# Buck.net
KiCad netlist of a schematic drawn in Altium Designer
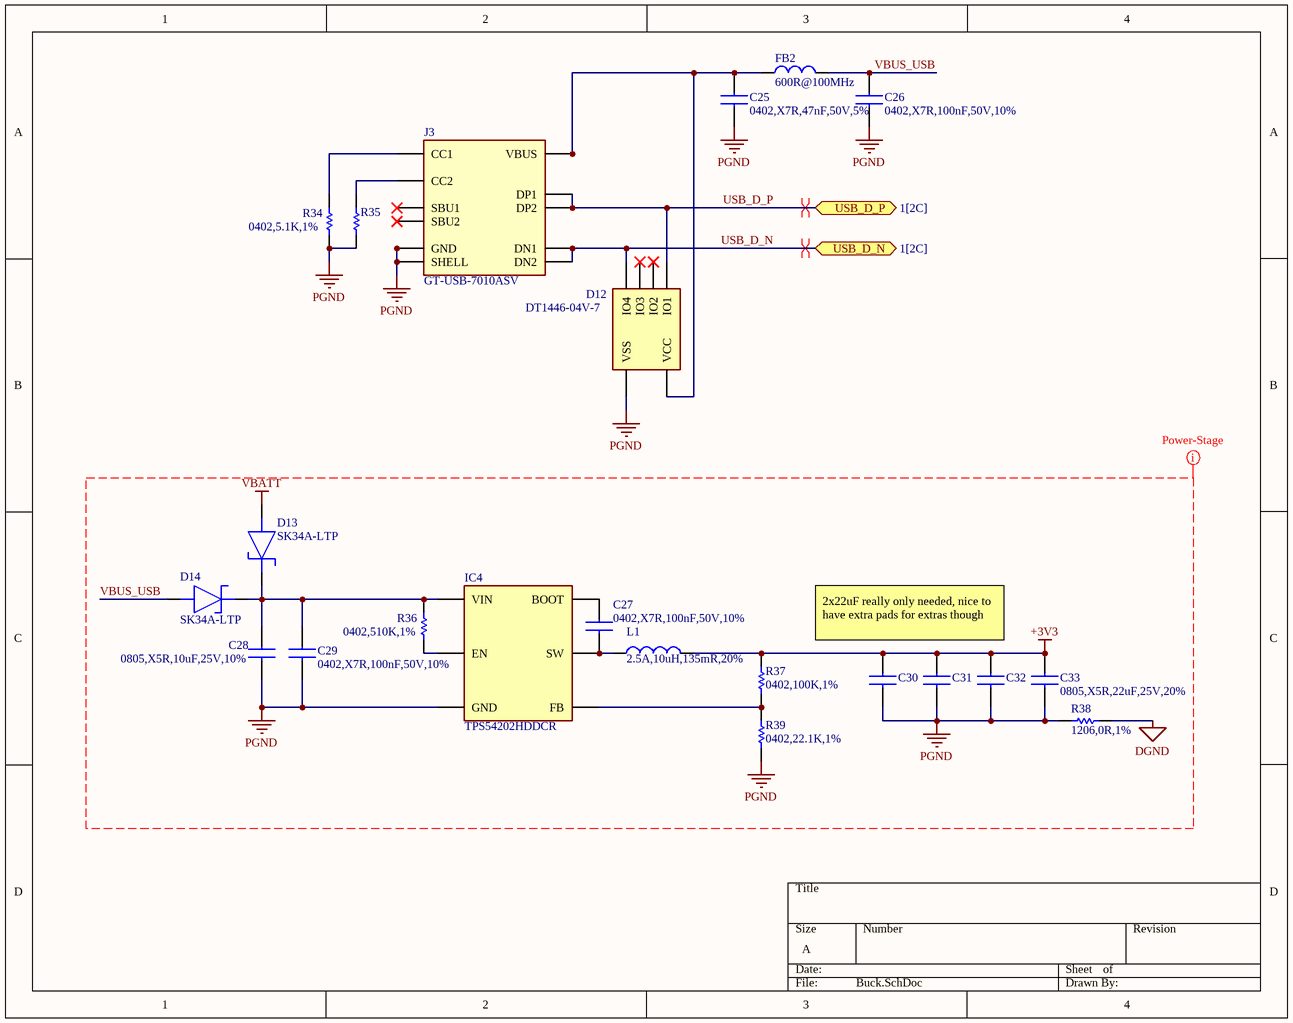
[diagram p0: Buck.SchDoc]

(export (version "E")
  (design (tool "Eeschema 10.0.6"))
  (components
    (comp (ref "C25")
      (value "0402,X7R,47nF,50V,5%")
      (footprint "CAPC1005X55N")
      (description "0.047 µF ±5% 50V Ceramic Capacitor X7R 0402 (1005 Metric)")
      (fields
        (field (name "MANUFACTURER_PART_NUMBER") "CC0402JRX7R9BB473")
        (field (name "MOUSER PART NUMBER") "603-CC402KRX7R9BB104")
      )
      (libsource (lib "ESC") (part "CC0402JRX7R9BB473"))
    )
    (comp (ref "C26")
      (value "0402,X7R,100nF,50V,10%")
      (footprint "CAPC1005X55N")
      (description "0.1 µF ±10% 50V Ceramic Capacitor X7R 0402 (1005 Metric)")
      (fields
        (field (name "MANUFACTURER_PART_NUMBER") "CC0402KRX7R9BB104")
        (field (name "MOUSER PART NUMBER") "603-CC402KRX7R9BB104")
      )
      (libsource (lib "ESC") (part "CC0402KRX7R9BB104"))
    )
    (comp (ref "C27")
      (value "0402,X7R,100nF,50V,10%")
      (footprint "CAPC1005X55N")
      (description "0.1 µF ±10% 50V Ceramic Capacitor X7R 0402 (1005 Metric)")
      (fields
        (field (name "MANUFACTURER_PART_NUMBER") "CC0402KRX7R9BB104")
        (field (name "MOUSER PART NUMBER") "603-CC402KRX7R9BB104")
      )
      (libsource (lib "ESC") (part "CC0402KRX7R9BB104"))
    )
    (comp (ref "C28")
      (value "0805,X5R,10uF,25V,10%")
      (footprint "CAPC2012X145N")
      (description "10 µF ±10% 25V Ceramic Capacitor X5R 0805 (2012 Metric)")
      (fields
        (field (name "MANUFACTURER_PART_NUMBER") "CC0805KKX5R8BB106")
        (field (name "MOUSER PART NUMBER") "603-CC805KKX5R8BB106")
      )
      (libsource (lib "ESC") (part "CC0805KKX5R8BB106"))
    )
    (comp (ref "C29")
      (value "0402,X7R,100nF,50V,10%")
      (footprint "CAPC1005X55N")
      (description "0.1 µF ±10% 50V Ceramic Capacitor X7R 0402 (1005 Metric)")
      (fields
        (field (name "MANUFACTURER_PART_NUMBER") "CC0402KRX7R9BB104")
        (field (name "MOUSER PART NUMBER") "603-CC402KRX7R9BB104")
      )
      (libsource (lib "ESC") (part "CC0402KRX7R9BB104"))
    )
    (comp (ref "C30")
      (value "0805,X5R,22uF,25V,20%")
      (footprint "CAPC2012X145N")
      (description "25V 22uF X5R ±20% 0805 Ceramic Capacitors RoHS")
      (fields
        (field (name "MANUFACTURER_PART_NUMBER") "CC0805MKX5R8BB226")
        (field (name "MOUSER PART NUMBER") "603-CC805KKX5R8BB106")
      )
      (libsource (lib "ESC") (part "CC0805MKX5R8BB226"))
    )
    (comp (ref "C31")
      (value "0805,X5R,22uF,25V,20%")
      (footprint "CAPC2012X145N")
      (description "25V 22uF X5R ±20% 0805 Ceramic Capacitors RoHS")
      (fields
        (field (name "MANUFACTURER_PART_NUMBER") "CC0805MKX5R8BB226")
        (field (name "MOUSER PART NUMBER") "603-CC805KKX5R8BB106")
      )
      (libsource (lib "ESC") (part "CC0805MKX5R8BB226"))
    )
    (comp (ref "C32")
      (value "0805,X5R,22uF,25V,20%")
      (footprint "CAPC2012X145N")
      (description "25V 22uF X5R ±20% 0805 Ceramic Capacitors RoHS")
      (fields
        (field (name "MANUFACTURER_PART_NUMBER") "CC0805MKX5R8BB226")
        (field (name "MOUSER PART NUMBER") "603-CC805KKX5R8BB106")
      )
      (libsource (lib "ESC") (part "CC0805MKX5R8BB226"))
    )
    (comp (ref "C33")
      (value "0805,X5R,22uF,25V,20%")
      (footprint "CAPC2012X145N")
      (description "25V 22uF X5R ±20% 0805 Ceramic Capacitors RoHS")
      (fields
        (field (name "MANUFACTURER_PART_NUMBER") "CC0805MKX5R8BB226")
        (field (name "MOUSER PART NUMBER") "603-CC805KKX5R8BB106")
      )
      (libsource (lib "ESC") (part "CC0805MKX5R8BB226"))
    )
    (comp (ref "D12")
      (value "DT1446-04V-7")
      (footprint "SOTFL50P162X60-6N")
      (description "8.5V Clamp 4.7A (8/20µs) Ipp Tvs Diode Surface Mount SOT-563")
      (fields (field (name "MOUSER PART NUMBER") "621-DT1446-04V-7") (field (name "LCSC PART #") "C460066"))
      (libsource (lib "ESC") (part "DT1446-04V-7"))
    )
    (comp (ref "D13")
      (value "SK34A-LTP")
      (footprint "SK34ALTP")
      (description "80A 40V 500mV@3A 3A SMA(DO-214AC) Single Diodes RoHS")
      (fields (field (name "MOUSER PART NUMBER") "833-SK34A-LTP") (field (name "LCSC PART #") "C85269"))
      (libsource (lib "ESC") (part "SK34A-LTP"))
    )
    (comp (ref "D14")
      (value "SK34A-LTP")
      (footprint "SK34ALTP")
      (description "80A 40V 500mV@3A 3A SMA(DO-214AC) Single Diodes RoHS")
      (fields (field (name "MOUSER PART NUMBER") "833-SK34A-LTP") (field (name "LCSC PART #") "C85269"))
      (libsource (lib "ESC") (part "SK34A-LTP"))
    )
    (comp (ref "FB2")
      (value "600R@100MHz")
      (footprint "L0603")
      (description "380mΩ ±25% 600Ω@100MHz 0603 Ferrite Beads ROHS")
      (fields (field (name "LCSC PART #") "C19330"))
      (libsource (lib "ESC") (part "BLM18AG601SN1D"))
    )
    (comp (ref "IC4")
      (value "TPS54202HDDCR")
      (footprint "SOT95P280X100-6N")
      (fields (field (name "MOUSER PART NUMBER") "595-TPS54202HDDCR") (field (name "LCSC PART #") "C527684"))
      (libsource (lib "ESC") (part "TPS54202HDDCR"))
    )
    (comp (ref "J3")
      (value "GT-USB-7010ASV")
      (footprint "USB-C-SMD_G-SWITCH_GT-USB-7010ASV")
      (description "USB 2.0 3A 1 Surface Mount, Right Angle 16P Female -40℃~+85℃ Type-C SMD USB Connectors ROHS")
      (fields (field (name "LCSC PART #") "C2988369"))
      (libsource (lib "ESC") (part "GT-USB-7010ASV"))
    )
    (comp (ref "L1")
      (value "2.5A,10uH,135mR,20%")
      (footprint "IND-SMD_L3.0-W3.0_FTC303020D")
      (description "2.5A 10uH ±20% 3.8A 135mΩ SMD,3x3mm Fixed Inductors RoHS")
      (fields (field (name "MANU PART #") "FTC303020D100MBCA") (field (name "LCSC PART #") "C7423323"))
      (libsource (lib "ESC") (part "FTC303020D100MBCA"))
    )
    (comp (ref "R34")
      (value "0402,5.1K,1%")
      (footprint "RESC1005X40N")
      (description "5.1 kOhms ±1% 0.063W, 1/16W Chip Resistor 0402 (1005 Metric) Moisture Resistant Thick Film")
      (fields
        (field (name "MANUFACTURER_PART_NUMBER") "RC0402FR-0710KL")
        (field (name "MOUSER PART NUMBER") "603-RC0402FR-0710KL")
      )
      (libsource (lib "ESC") (part "RC0402FR-075K1L"))
    )
    (comp (ref "R35")
      (value "0402,5.1K,1%")
      (footprint "RESC1005X40N")
      (description "5.1 kOhms ±1% 0.063W, 1/16W Chip Resistor 0402 (1005 Metric) Moisture Resistant Thick Film")
      (fields
        (field (name "MANUFACTURER_PART_NUMBER") "RC0402FR-0710KL")
        (field (name "MOUSER PART NUMBER") "603-RC0402FR-0710KL")
      )
      (libsource (lib "ESC") (part "RC0402FR-075K1L"))
    )
    (comp (ref "R36")
      (value "0402,510K,1%")
      (footprint "RESC1005X40N")
      (description "510 kOhms ±1% 0.063W, 1/16W Chip Resistor 0402 (1005 Metric) Moisture Resistant Thick Film")
      (fields
        (field (name "MANUFACTURER_PART_NUMBER") "RC0402FR-0710KL")
        (field (name "MOUSER PART NUMBER") "603-RC0402FR-0710KL")
      )
      (libsource (lib "ESC") (part "RC0402FR-07510KL"))
    )
    (comp (ref "R37")
      (value "0402,100K,1%")
      (footprint "RESC1005X40N")
      (description "100 kOhms ±1% 0.063W, 1/16W Chip Resistor 0402 (1005 Metric) Moisture Resistant Thick Film")
      (fields
        (field (name "MANUFACTURER_PART_NUMBER") "RC0402FR-0710KL")
        (field (name "MOUSER PART NUMBER") "603-RC0402FR-0710KL")
      )
      (libsource (lib "ESC") (part "RC0402FR-07100KL"))
    )
    (comp (ref "R38")
      (value "1206,0R,1%")
      (footprint "RESC3116X65N")
      (description "0Ω 250mW 200V Thick Film Resistor ±1% 1206 Chip Resistor - Surface Mount RoHS")
      (fields
        (field (name "MANUFACTURER_PART_NUMBER") "RC1206FR-070RL")
        (field (name "MOUSER PART NUMBER") "603-RC1206FR-070RL")
      )
      (libsource (lib "ESC") (part "RC1206FR-070RL"))
    )
    (comp (ref "R39")
      (value "0402,22.1K,1%")
      (footprint "RESC1005X40N")
      (description "22.1 kOhms ±1% 0.063W, 1/16W Chip Resistor 0402 (1005 Metric) Moisture Resistant Thick Film")
      (fields
        (field (name "MANUFACTURER_PART_NUMBER") "RC0402FR-0710KL")
        (field (name "MOUSER PART NUMBER") "603-RC0402FR-0710KL")
      )
      (libsource (lib "ESC") (part "RC0402FR-0722K1L"))
    )
  )
  (nets
    (net (code "1") (name "+3V3") (class "Default")
      (node (ref "C30") (pin "2") (pinfunction "2_2") (pintype "passive"))
      (node (ref "C31") (pin "2") (pinfunction "2_2") (pintype "passive"))
      (node (ref "C32") (pin "2") (pinfunction "2_2") (pintype "passive"))
      (node (ref "C33") (pin "2") (pinfunction "2_2") (pintype "passive"))
      (node (ref "L1") (pin "2") (pinfunction "2_2") (pintype "passive"))
      (node (ref "R37") (pin "2") (pinfunction "2_2") (pintype "passive"))
    )
    (net (code "2") (name "/USB_D_N") (class "Default")
      (node (ref "D12") (pin "6") (pinfunction "IO4_6") (pintype "passive"))
      (node (ref "J3") (pin "A7") (pinfunction "DN1_A7") (pintype "passive"))
      (node (ref "J3") (pin "B7") (pinfunction "DN2_B7") (pintype "passive"))
    )
    (net (code "3") (name "/USB_D_P") (class "Default")
      (node (ref "D12") (pin "1") (pinfunction "IO1_1") (pintype "passive"))
      (node (ref "J3") (pin "A6") (pinfunction "DP1_A6") (pintype "passive"))
      (node (ref "J3") (pin "B6") (pinfunction "DP2_B6") (pintype "passive"))
    )
    (net (code "4") (name "/VBUS_USB") (class "Default")
      (node (ref "C26") (pin "2") (pinfunction "2_2") (pintype "passive"))
      (node (ref "D14") (pin "2") (pinfunction "A_2") (pintype "passive"))
      (node (ref "FB2") (pin "2") (pinfunction "2_2") (pintype "passive"))
    )
    (net (code "5") (name "DGND") (class "Default")
      (node (ref "R38") (pin "2") (pinfunction "2_2") (pintype "passive"))
    )
    (net (code "6") (name "Net-(D12-VCC)") (class "Default")
      (node (ref "C25") (pin "2") (pinfunction "2_2") (pintype "passive"))
      (node (ref "D12") (pin "5") (pinfunction "VCC_5") (pintype "passive"))
      (node (ref "FB2") (pin "1") (pinfunction "1_1") (pintype "passive"))
      (node (ref "J3") (pin "A4B9") (pinfunction "VBUS_A4B9") (pintype "passive"))
      (node (ref "J3") (pin "B4A9") (pinfunction "VBUS_B4A9") (pintype "passive"))
    )
    (net (code "7") (name "Net-(D13-K)") (class "Default")
      (node (ref "C28") (pin "2") (pinfunction "2_2") (pintype "passive"))
      (node (ref "C29") (pin "2") (pinfunction "2_2") (pintype "passive"))
      (node (ref "D13") (pin "1") (pinfunction "K_1") (pintype "passive"))
      (node (ref "D14") (pin "1") (pinfunction "K_1") (pintype "passive"))
      (node (ref "IC4") (pin "3") (pinfunction "VIN_3") (pintype "passive"))
      (node (ref "R36") (pin "2") (pinfunction "2_2") (pintype "passive"))
    )
    (net (code "8") (name "Net-(IC4-BOOT)") (class "Default")
      (node (ref "C27") (pin "2") (pinfunction "2_2") (pintype "passive"))
      (node (ref "IC4") (pin "6") (pinfunction "BOOT_6") (pintype "passive"))
    )
    (net (code "9") (name "Net-(IC4-EN)") (class "Default")
      (node (ref "IC4") (pin "5") (pinfunction "EN_5") (pintype "passive"))
      (node (ref "R36") (pin "1") (pinfunction "1_1") (pintype "passive"))
    )
    (net (code "10") (name "Net-(IC4-FB)") (class "Default")
      (node (ref "IC4") (pin "4") (pinfunction "FB_4") (pintype "passive"))
      (node (ref "R37") (pin "1") (pinfunction "1_1") (pintype "passive"))
      (node (ref "R39") (pin "2") (pinfunction "2_2") (pintype "passive"))
    )
    (net (code "11") (name "Net-(IC4-SW)") (class "Default")
      (node (ref "C27") (pin "1") (pinfunction "1_1") (pintype "passive"))
      (node (ref "IC4") (pin "2") (pinfunction "SW_2") (pintype "passive"))
      (node (ref "L1") (pin "1") (pinfunction "1_1") (pintype "passive"))
    )
    (net (code "12") (name "Net-(J3-CC1)") (class "Default")
      (node (ref "J3") (pin "A5") (pinfunction "CC1_A5") (pintype "passive"))
      (node (ref "R34") (pin "2") (pinfunction "2_2") (pintype "passive"))
    )
    (net (code "13") (name "Net-(J3-CC2)") (class "Default")
      (node (ref "J3") (pin "B5") (pinfunction "CC2_B5") (pintype "passive"))
      (node (ref "R35") (pin "2") (pinfunction "2_2") (pintype "passive"))
    )
    (net (code "14") (name "PGND") (class "Default")
      (node (ref "C25") (pin "1") (pinfunction "1_1") (pintype "passive"))
      (node (ref "C26") (pin "1") (pinfunction "1_1") (pintype "passive"))
      (node (ref "C28") (pin "1") (pinfunction "1_1") (pintype "passive"))
      (node (ref "C29") (pin "1") (pinfunction "1_1") (pintype "passive"))
      (node (ref "C30") (pin "1") (pinfunction "1_1") (pintype "passive"))
      (node (ref "C31") (pin "1") (pinfunction "1_1") (pintype "passive"))
      (node (ref "C32") (pin "1") (pinfunction "1_1") (pintype "passive"))
      (node (ref "C33") (pin "1") (pinfunction "1_1") (pintype "passive"))
      (node (ref "D12") (pin "2") (pinfunction "VSS_2") (pintype "passive"))
      (node (ref "IC4") (pin "1") (pinfunction "GND_1") (pintype "passive"))
      (node (ref "J3") (pin "1") (pinfunction "SHELL_1") (pintype "passive"))
      (node (ref "J3") (pin "2") (pinfunction "SHELL_2") (pintype "passive"))
      (node (ref "J3") (pin "3") (pinfunction "SHELL_3") (pintype "passive"))
      (node (ref "J3") (pin "4") (pinfunction "SHELL_4") (pintype "passive"))
      (node (ref "J3") (pin "A1B12") (pinfunction "GND_A1B12") (pintype "passive"))
      (node (ref "J3") (pin "B1A12") (pinfunction "GND_B1A12") (pintype "passive"))
      (node (ref "R34") (pin "1") (pinfunction "1_1") (pintype "passive"))
      (node (ref "R35") (pin "1") (pinfunction "1_1") (pintype "passive"))
      (node (ref "R38") (pin "1") (pinfunction "1_1") (pintype "passive"))
      (node (ref "R39") (pin "1") (pinfunction "1_1") (pintype "passive"))
    )
    (net (code "15") (name "VBATT") (class "Default")
      (node (ref "D13") (pin "2") (pinfunction "A_2") (pintype "passive"))
    )
    (net (code "16") (name "unconnected-(D12-IO2-Pad3)") (class "Default")
      (node (ref "D12") (pin "3") (pinfunction "IO2_3") (pintype "passive+no_connect"))
    )
    (net (code "17") (name "unconnected-(D12-IO3-Pad4)") (class "Default")
      (node (ref "D12") (pin "4") (pinfunction "IO3_4") (pintype "passive+no_connect"))
    )
    (net (code "18") (name "unconnected-(J3-SBU1-PadA8)") (class "Default")
      (node (ref "J3") (pin "A8") (pinfunction "SBU1_A8") (pintype "passive+no_connect"))
    )
    (net (code "19") (name "unconnected-(J3-SBU2-PadB8)") (class "Default")
      (node (ref "J3") (pin "B8") (pinfunction "SBU2_B8") (pintype "passive+no_connect"))
    )
  )
)
